# handle.net
KiCad netlist of a schematic drawn in EAGLE
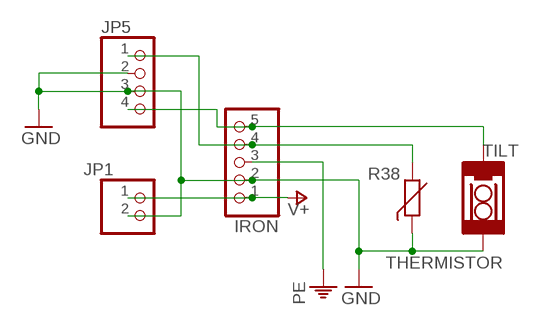
[diagram p0: schematic, sheet 1]

(export (version "E")
  (design (tool "Eeschema 10.0.6"))
  (components
    (comp (ref "IRON")
      (value "PINHD-1X5")
      (footprint "eagle-import:1X05")
      (libsource (lib "eagle-import") (part "PINHD-1X5"))
    )
    (comp (ref "JP1")
      (value "PINHD-1X2")
      (footprint "eagle-import:1X02")
      (libsource (lib "eagle-import") (part "PINHD-1X2"))
    )
    (comp (ref "JP5")
      (value "PINHD-1X4")
      (footprint "eagle-import:1X04")
      (libsource (lib "eagle-import") (part "PINHD-1X4"))
    )
    (comp (ref "R38")
      (value "THERMISTOR")
      (footprint "eagle-import:RS-2,5")
      (libsource (lib "eagle-import") (part "THERMISTOR_R-2,5"))
    )
    (comp (ref "TILT")
      (value "SQ-SEN-200")
      (footprint "eagle-import:SQ-SEN-200")
      (libsource (lib "eagle-import") (part "SQ-SEN-200"))
    )
  )
  (nets
    (net (code "1") (name "GND") (class "Default")
      (node (ref "IRON") (pin "2") (pinfunction "2_2") (pintype "passive"))
      (node (ref "JP1") (pin "2") (pinfunction "2_2") (pintype "passive"))
      (node (ref "JP5") (pin "2") (pinfunction "2_2") (pintype "passive"))
      (node (ref "JP5") (pin "3") (pinfunction "3_3") (pintype "passive"))
      (node (ref "R38") (pin "1") (pinfunction "1_1") (pintype "passive"))
      (node (ref "TILT") (pin "2") (pinfunction "2_2") (pintype "passive"))
    )
    (net (code "2") (name "Net-(IRON-Pad4)") (class "Default")
      (node (ref "IRON") (pin "4") (pinfunction "4_4") (pintype "passive"))
      (node (ref "JP5") (pin "1") (pinfunction "1_1") (pintype "passive"))
      (node (ref "R38") (pin "2") (pinfunction "2_2") (pintype "passive"))
    )
    (net (code "3") (name "Net-(IRON-Pad5)") (class "Default")
      (node (ref "IRON") (pin "5") (pinfunction "5_5") (pintype "passive"))
      (node (ref "JP5") (pin "4") (pinfunction "4_4") (pintype "passive"))
      (node (ref "TILT") (pin "1") (pinfunction "1_1") (pintype "passive"))
    )
    (net (code "4") (name "PE") (class "Default")
      (node (ref "IRON") (pin "3") (pinfunction "3_3") (pintype "passive"))
    )
    (net (code "5") (name "V+") (class "Default")
      (node (ref "IRON") (pin "1") (pinfunction "1_1") (pintype "passive"))
      (node (ref "JP1") (pin "1") (pinfunction "1_1") (pintype "passive"))
    )
  )
)
